# Sheet1.net
KiCad netlist of a schematic drawn in Altium Designer
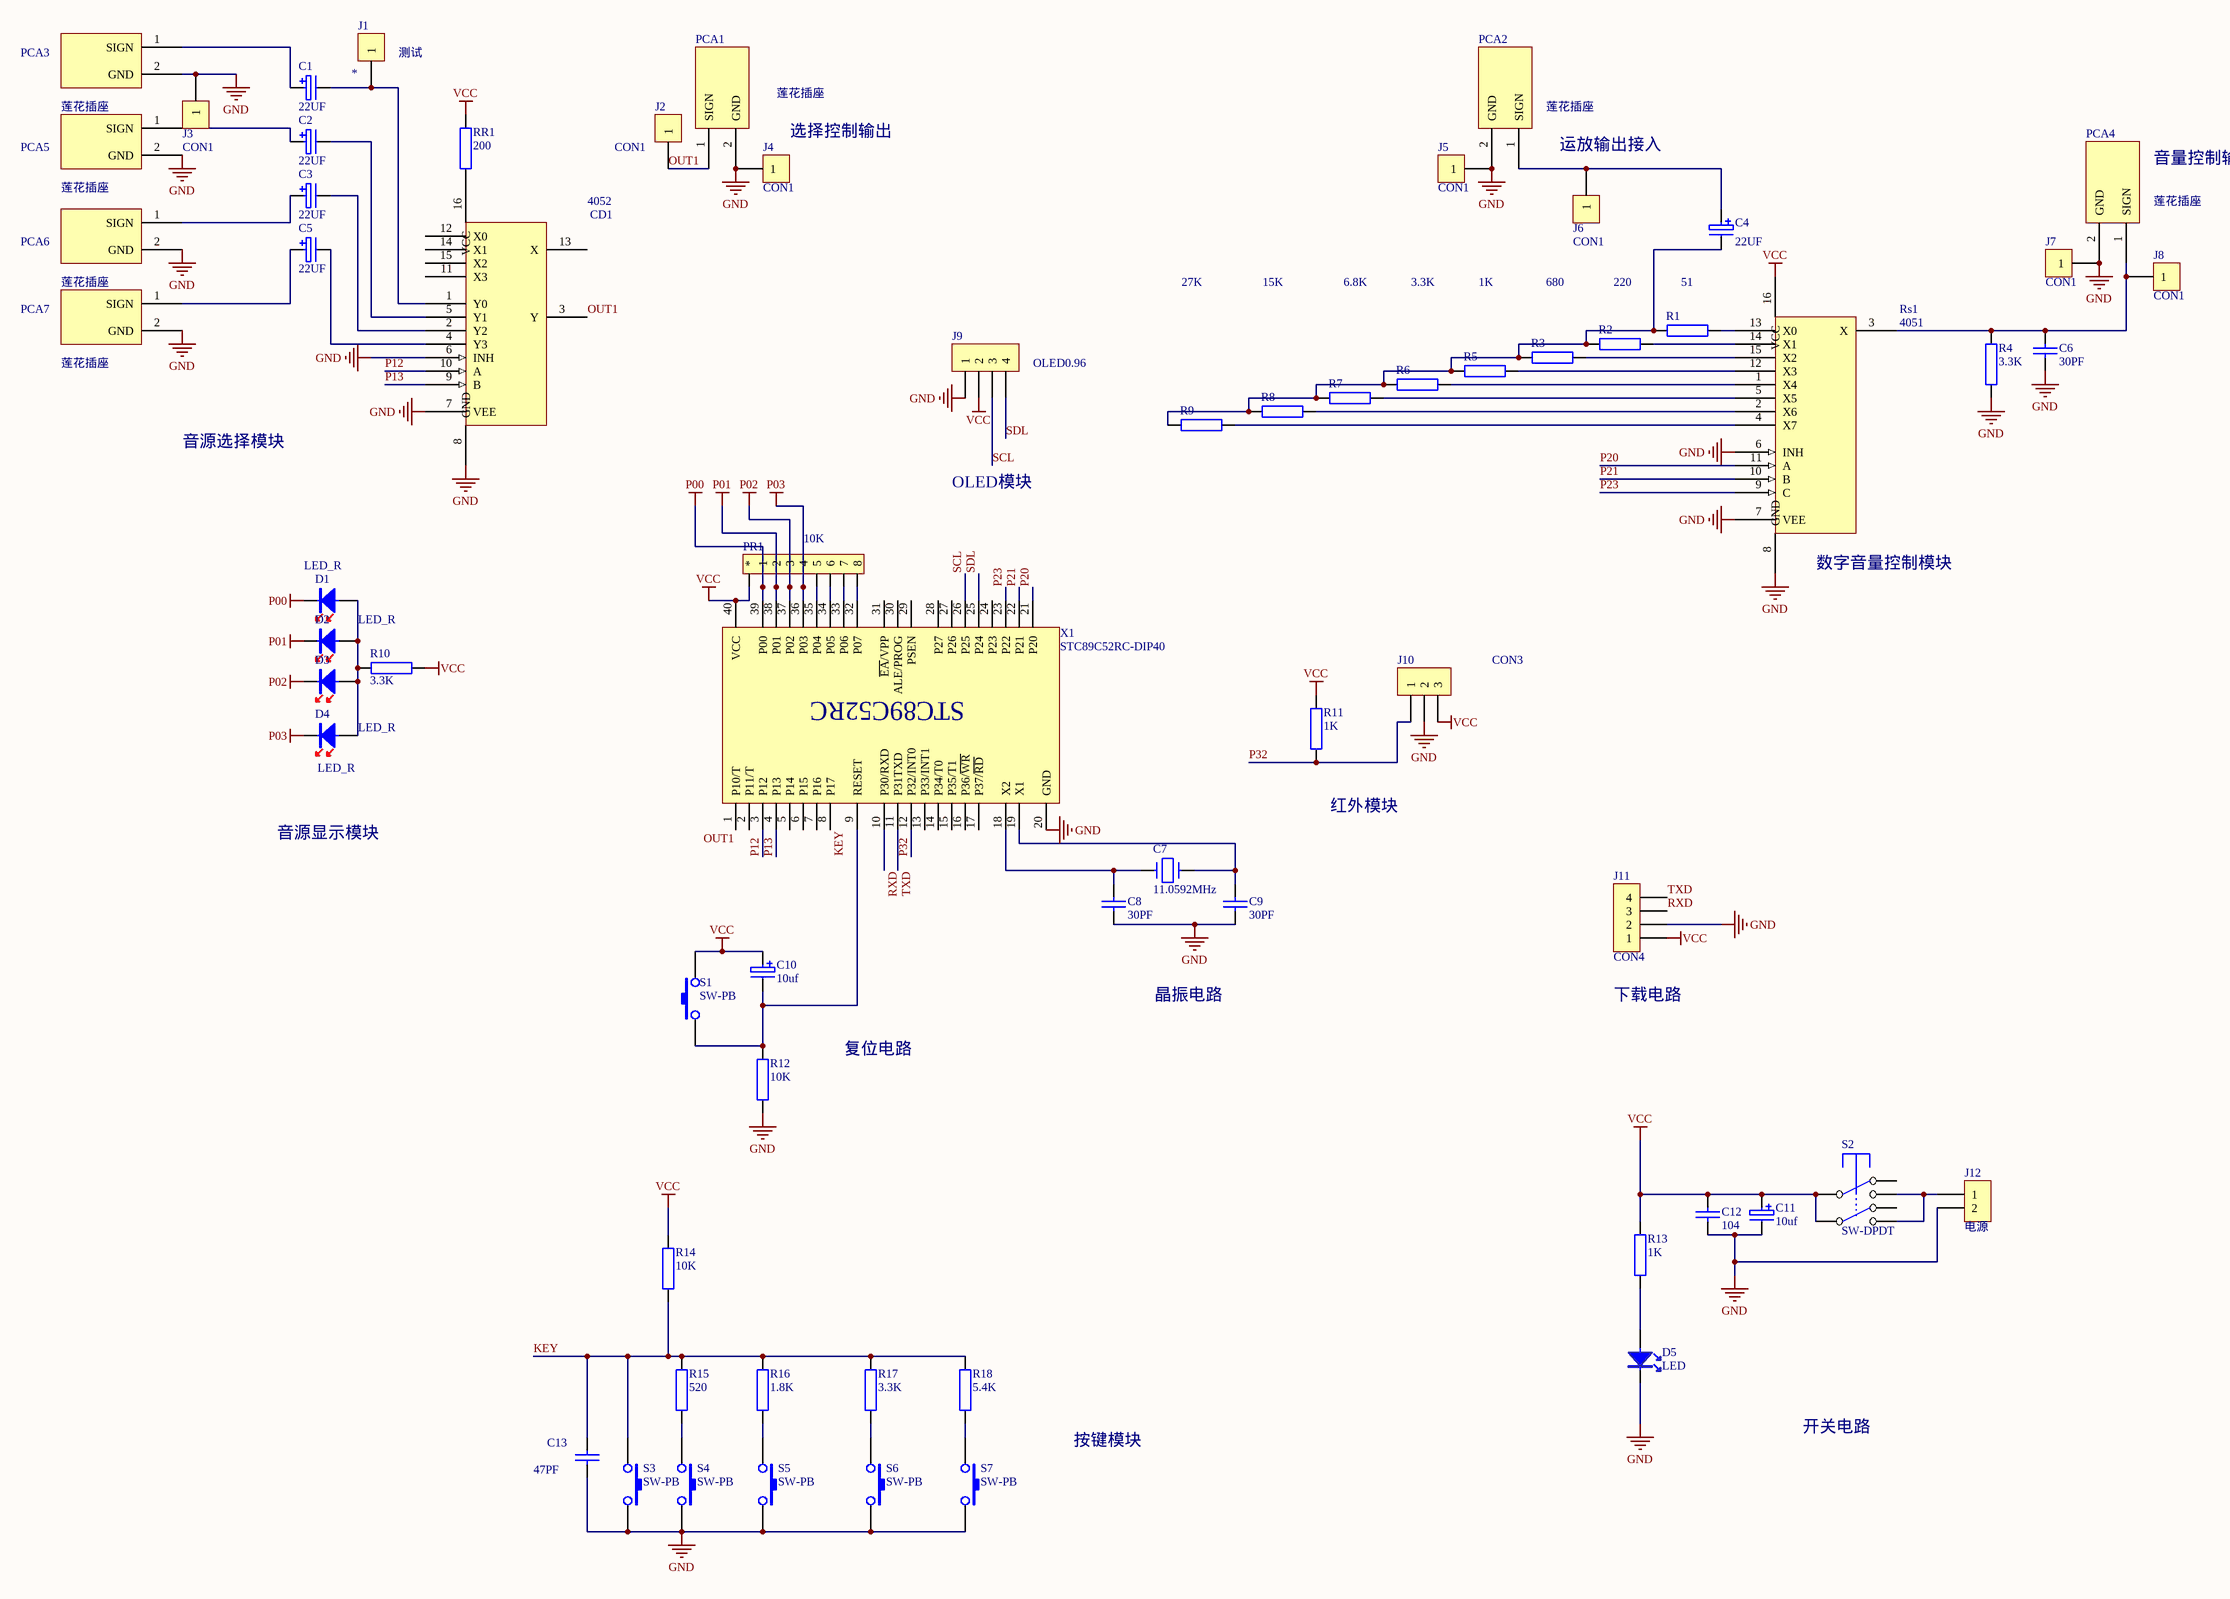
[diagram p0: Sheet1.SchDoc]

(export (version "E")
  (design (tool "Eeschema 10.0.6"))
  (components
    (comp (ref "C1") (value "22UF") (footprint "CAO2") (libsource (lib "电容") (part "CAP3")))
    (comp (ref "C2") (value "22UF") (footprint "CAO2") (libsource (lib "电容") (part "CAP3")))
    (comp (ref "C3") (value "22UF") (footprint "CAO2") (libsource (lib "电容") (part "CAP3")))
    (comp (ref "C4") (value "22UF") (footprint "CAO2") (libsource (lib "电容") (part "CAP3")))
    (comp (ref "C5") (value "22UF") (footprint "CAO2") (libsource (lib "电容") (part "CAP3")))
    (comp (ref "C6") (value "30PF") (footprint "CAP2") (libsource (lib "电容") (part "CAP1")))
    (comp (ref "C7") (value "11.0592MHz") (footprint "XTAL1") (libsource (lib "晶振") (part "CPY")))
    (comp (ref "C8") (value "30PF") (footprint "CAP2") (libsource (lib "电容") (part "CAP1")))
    (comp (ref "C9") (value "30PF") (footprint "CAP2") (libsource (lib "电容") (part "CAP1")))
    (comp (ref "C10") (value "10uf") (footprint "CAO2") (libsource (lib "电容") (part "CAP3")))
    (comp (ref "C11") (value "10uf") (footprint "CAO2") (libsource (lib "电容") (part "CAP3")))
    (comp (ref "C12") (value "104") (footprint "CAP2") (libsource (lib "电容") (part "CAP1")))
    (comp (ref "C13") (value "47PF") (footprint "CAP2") (libsource (lib "电容") (part "CAP1")))
    (comp (ref "CD1") (value "4052") (footprint "SO-16") (libsource (lib "51库") (part "4052")))
    (comp (ref "D1") (value "LED_R") (footprint "LED2_B") (libsource (lib "Diode二极管") (part "LED_R")))
    (comp (ref "D2") (value "LED_R") (footprint "LED2_B") (libsource (lib "Diode二极管") (part "LED_R")))
    (comp (ref "D3") (value "LED_R") (footprint "LED2_B") (libsource (lib "Diode二极管") (part "LED_R")))
    (comp (ref "D4") (value "LED_R") (footprint "LED2_B") (libsource (lib "Diode二极管") (part "LED_R")))
    (comp (ref "D5") (value "LED") (footprint "LED2_B") (libsource (lib "二极管") (part "LED")))
    (comp (ref "J1")
      (value "*")
      (footprint "SIP-1")
      (description "Connector")
      (fields (field (name "测试") "测试"))
      (libsource (lib "") (part "CON1_2"))
    )
    (comp (ref "J2")
      (value "CON1")
      (footprint "SIP-1")
      (description "Connector")
      (libsource (lib "") (part "CON1_2"))
    )
    (comp (ref "J3")
      (value "CON1")
      (footprint "SIP-1")
      (description "Connector")
      (libsource (lib "排针") (part "测试"))
    )
    (comp (ref "J4")
      (value "CON1")
      (footprint "SIP-1")
      (description "Connector")
      (libsource (lib "") (part "CON1_3"))
    )
    (comp (ref "J5")
      (value "CON1")
      (footprint "SIP-1")
      (description "Connector")
      (libsource (lib "") (part "CON1_1"))
    )
    (comp (ref "J6")
      (value "CON1")
      (footprint "SIP-1")
      (description "Connector")
      (libsource (lib "排针") (part "CON1"))
    )
    (comp (ref "J7")
      (value "CON1")
      (footprint "SIP-1")
      (description "Connector")
      (libsource (lib "") (part "CON1_1"))
    )
    (comp (ref "J8")
      (value "CON1")
      (footprint "SIP-1")
      (description "Connector")
      (libsource (lib "") (part "CON1_3"))
    )
    (comp (ref "J9")
      (value "OLED0.96")
      (footprint "sip-4")
      (description "Connector")
      (libsource (lib "排针") (part "CON4"))
    )
    (comp (ref "J10")
      (value "CON3")
      (footprint "sip-3")
      (description "Connector")
      (libsource (lib "排针") (part "CON3"))
    )
    (comp (ref "J11")
      (value "CON4")
      (footprint "sip-4")
      (description "Connector")
      (libsource (lib "") (part "CON4_1"))
    )
    (comp (ref "J12")
      (value "电源")
      (footprint "接线端子")
      (description "Connector")
      (libsource (lib "排针") (part "CON2"))
    )
    (comp (ref "PCA1") (value "莲花插座") (footprint "莲花母座") (libsource (lib "") (part "PCA_2")))
    (comp (ref "PCA2") (value "莲花插座") (footprint "莲花母座") (libsource (lib "") (part "PCA_1")))
    (comp (ref "PCA3") (value "莲花插座") (footprint "莲花母座") (libsource (lib "音频功放自画库") (part "PCA")))
    (comp (ref "PCA4") (value "莲花插座") (footprint "莲花母座") (libsource (lib "") (part "PCA_1")))
    (comp (ref "PCA5") (value "莲花插座") (footprint "莲花母座") (libsource (lib "音频功放自画库") (part "PCA")))
    (comp (ref "PCA6") (value "莲花插座") (footprint "莲花母座") (libsource (lib "音频功放自画库") (part "PCA")))
    (comp (ref "PCA7") (value "莲花插座") (footprint "莲花母座") (libsource (lib "音频功放自画库") (part "PCA")))
    (comp (ref "PR1") (value "10K") (footprint "RP1") (libsource (lib "电阻") (part "PRES1")))
    (comp (ref "R1")
      (value "51")
      (footprint "AXIAL0.4")
      (description "电阻")
      (libsource (lib "电阻") (part "RES"))
    )
    (comp (ref "R2")
      (value "220")
      (footprint "AXIAL0.4")
      (description "电阻")
      (libsource (lib "电阻") (part "RES"))
    )
    (comp (ref "R3")
      (value "680")
      (footprint "AXIAL0.4")
      (description "电阻")
      (libsource (lib "电阻") (part "RES"))
    )
    (comp (ref "R4")
      (value "3.3K")
      (footprint "AXIAL0.4")
      (description "电阻")
      (libsource (lib "电阻") (part "RES"))
    )
    (comp (ref "R5")
      (value "1K")
      (footprint "AXIAL0.4")
      (description "电阻")
      (libsource (lib "电阻") (part "RES"))
    )
    (comp (ref "R6")
      (value "3.3K")
      (footprint "AXIAL0.4")
      (description "电阻")
      (libsource (lib "电阻") (part "RES"))
    )
    (comp (ref "R7")
      (value "6.8K")
      (footprint "AXIAL0.4")
      (description "电阻")
      (libsource (lib "电阻") (part "RES"))
    )
    (comp (ref "R8")
      (value "15K")
      (footprint "AXIAL0.4")
      (description "电阻")
      (libsource (lib "电阻") (part "RES"))
    )
    (comp (ref "R9")
      (value "27K")
      (footprint "AXIAL0.4")
      (description "电阻")
      (libsource (lib "电阻") (part "RES"))
    )
    (comp (ref "R10")
      (value "3.3K")
      (footprint "AXIAL0.4")
      (description "电阻")
      (libsource (lib "电阻") (part "RES"))
    )
    (comp (ref "R11")
      (value "1K")
      (footprint "AXIAL0.4")
      (description "电阻")
      (libsource (lib "电阻") (part "RES"))
    )
    (comp (ref "R12")
      (value "10K")
      (footprint "AXIAL0.4")
      (description "电阻")
      (libsource (lib "电阻") (part "RES"))
    )
    (comp (ref "R13")
      (value "1K")
      (footprint "AXIAL0.4")
      (description "电阻")
      (libsource (lib "电阻") (part "RES"))
    )
    (comp (ref "R14")
      (value "10K")
      (footprint "AXIAL0.4")
      (description "电阻")
      (libsource (lib "电阻") (part "RES"))
    )
    (comp (ref "R15")
      (value "520")
      (footprint "AXIAL0.4")
      (description "电阻")
      (libsource (lib "电阻") (part "RES"))
    )
    (comp (ref "R16")
      (value "1.8K")
      (footprint "AXIAL0.4")
      (description "电阻")
      (libsource (lib "电阻") (part "RES"))
    )
    (comp (ref "R17")
      (value "3.3K")
      (footprint "AXIAL0.4")
      (description "电阻")
      (libsource (lib "电阻") (part "RES"))
    )
    (comp (ref "R18")
      (value "5.4K")
      (footprint "AXIAL0.4")
      (description "电阻")
      (libsource (lib "电阻") (part "RES"))
    )
    (comp (ref "RR1")
      (value "200")
      (footprint "AXIAL0.4")
      (description "电阻")
      (libsource (lib "电阻") (part "RES"))
    )
    (comp (ref "Rs1") (value "4051") (footprint "SO-16") (libsource (lib "51库") (part "4051")))
    (comp (ref "S1") (value "SW-PB") (footprint "SW6*6") (libsource (lib "开关") (part "SW-PB")))
    (comp (ref "S2") (value "SW-DPDT") (footprint "SWH8*8") (libsource (lib "开关") (part "SW-DPDT")))
    (comp (ref "S3") (value "SW-PB") (footprint "SW6*6") (libsource (lib "开关") (part "SW-PB")))
    (comp (ref "S4") (value "SW-PB") (footprint "SW6*6") (libsource (lib "开关") (part "SW-PB")))
    (comp (ref "S5") (value "SW-PB") (footprint "SW6*6") (libsource (lib "开关") (part "SW-PB")))
    (comp (ref "S6") (value "SW-PB") (footprint "SW6*6") (libsource (lib "开关") (part "SW-PB")))
    (comp (ref "S7") (value "SW-PB") (footprint "SW6*6") (libsource (lib "开关") (part "SW-PB")))
    (comp (ref "X1")
      (value "STC89C52RC-DIP40")
      (footprint "DIP-40")
      (libsource (lib "单片机") (part "STC89C52RC-DIP40"))
    )
  )
  (nets
    (net (code "1") (name "/KEY") (class "Default")
      (node (ref "C13") (pin "1") (pinfunction "1_1") (pintype "passive"))
      (node (ref "R14") (pin "1") (pinfunction "1_1") (pintype "passive"))
      (node (ref "R15") (pin "2") (pinfunction "2_2") (pintype "passive"))
      (node (ref "R16") (pin "2") (pinfunction "2_2") (pintype "passive"))
      (node (ref "R17") (pin "2") (pinfunction "2_2") (pintype "passive"))
      (node (ref "R18") (pin "2") (pinfunction "2_2") (pintype "passive"))
      (node (ref "S3") (pin "1") (pinfunction "1_1") (pintype "passive"))
      (node (ref "X1") (pin "8") (pinfunction "P17_8") (pintype "passive"))
    )
    (net (code "2") (name "/OUT1") (class "Default")
      (node (ref "CD1") (pin "3") (pinfunction "Y_3") (pintype "passive"))
      (node (ref "J2") (pin "1") (pinfunction "1_1") (pintype "passive"))
      (node (ref "PCA1") (pin "1") (pinfunction "SIGN_1") (pintype "passive"))
      (node (ref "X1") (pin "1") (pinfunction "P10/T_1") (pintype "passive"))
    )
    (net (code "3") (name "/P12") (class "Default")
      (node (ref "CD1") (pin "10") (pinfunction "A_10") (pintype "input"))
      (node (ref "X1") (pin "3") (pinfunction "P12_3") (pintype "passive"))
    )
    (net (code "4") (name "/P13") (class "Default")
      (node (ref "CD1") (pin "9") (pinfunction "B_9") (pintype "input"))
      (node (ref "X1") (pin "4") (pinfunction "P13_4") (pintype "passive"))
    )
    (net (code "5") (name "/P20") (class "Default")
      (node (ref "Rs1") (pin "11") (pinfunction "A_11") (pintype "input"))
      (node (ref "X1") (pin "21") (pinfunction "P20_21") (pintype "passive"))
    )
    (net (code "6") (name "/P21") (class "Default")
      (node (ref "Rs1") (pin "10") (pinfunction "B_10") (pintype "input"))
      (node (ref "X1") (pin "22") (pinfunction "P21_22") (pintype "passive"))
    )
    (net (code "7") (name "/P23") (class "Default")
      (node (ref "Rs1") (pin "9") (pinfunction "C_9") (pintype "input"))
      (node (ref "X1") (pin "23") (pinfunction "P22_23") (pintype "passive"))
    )
    (net (code "8") (name "/P32") (class "Default")
      (node (ref "J10") (pin "1") (pinfunction "1_1") (pintype "passive"))
      (node (ref "R11") (pin "1") (pinfunction "1_1") (pintype "passive"))
      (node (ref "X1") (pin "12") (pinfunction "P32/INT0_12") (pintype "passive"))
    )
    (net (code "9") (name "/RXD") (class "Default")
      (node (ref "J11") (pin "3") (pinfunction "3_3") (pintype "passive"))
      (node (ref "X1") (pin "10") (pinfunction "P30/RXD_10") (pintype "passive"))
    )
    (net (code "10") (name "/SCL") (class "Default")
      (node (ref "J9") (pin "3") (pinfunction "3_3") (pintype "passive"))
      (node (ref "X1") (pin "26") (pinfunction "P25_26") (pintype "passive"))
    )
    (net (code "11") (name "/SDL") (class "Default")
      (node (ref "J9") (pin "4") (pinfunction "4_4") (pintype "passive"))
      (node (ref "X1") (pin "25") (pinfunction "P24_25") (pintype "passive"))
    )
    (net (code "12") (name "/TXD") (class "Default")
      (node (ref "J11") (pin "4") (pinfunction "4_4") (pintype "passive"))
      (node (ref "X1") (pin "11") (pinfunction "P31TXD_11") (pintype "passive"))
    )
    (net (code "13") (name "GND") (class "Default")
      (node (ref "C11") (pin "2") (pintype "passive"))
      (node (ref "C12") (pin "2") (pinfunction "2_2") (pintype "passive"))
      (node (ref "C13") (pin "2") (pinfunction "2_2") (pintype "passive"))
      (node (ref "C6") (pin "2") (pinfunction "2_2") (pintype "passive"))
      (node (ref "C8") (pin "2") (pinfunction "2_2") (pintype "passive"))
      (node (ref "C9") (pin "2") (pinfunction "2_2") (pintype "passive"))
      (node (ref "CD1") (pin "6") (pinfunction "INH_6") (pintype "input"))
      (node (ref "CD1") (pin "7") (pinfunction "VEE_7") (pintype "passive"))
      (node (ref "CD1") (pin "8") (pinfunction "GND_8") (pintype "power_in"))
      (node (ref "D5") (pin "2") (pinfunction "2_2") (pintype "passive"))
      (node (ref "J10") (pin "2") (pinfunction "2_2") (pintype "passive"))
      (node (ref "J11") (pin "2") (pinfunction "2_2") (pintype "passive"))
      (node (ref "J12") (pin "2") (pinfunction "2_2") (pintype "passive"))
      (node (ref "J3") (pin "1") (pinfunction "1_1") (pintype "passive"))
      (node (ref "J4") (pin "1") (pinfunction "1_1") (pintype "passive"))
      (node (ref "J5") (pin "1") (pinfunction "1_1") (pintype "passive"))
      (node (ref "J7") (pin "1") (pinfunction "1_1") (pintype "passive"))
      (node (ref "J9") (pin "1") (pinfunction "1_1") (pintype "passive"))
      (node (ref "PCA1") (pin "2") (pinfunction "GND_2") (pintype "passive"))
      (node (ref "PCA2") (pin "2") (pinfunction "GND_2") (pintype "passive"))
      (node (ref "PCA3") (pin "2") (pinfunction "GND_2") (pintype "passive"))
      (node (ref "PCA4") (pin "2") (pinfunction "GND_2") (pintype "passive"))
      (node (ref "PCA5") (pin "2") (pinfunction "GND_2") (pintype "passive"))
      (node (ref "PCA6") (pin "2") (pinfunction "GND_2") (pintype "passive"))
      (node (ref "PCA7") (pin "2") (pinfunction "GND_2") (pintype "passive"))
      (node (ref "R12") (pin "1") (pinfunction "1_1") (pintype "passive"))
      (node (ref "R4") (pin "1") (pinfunction "1_1") (pintype "passive"))
      (node (ref "Rs1") (pin "6") (pinfunction "INH_6") (pintype "input"))
      (node (ref "Rs1") (pin "7") (pinfunction "VEE_7") (pintype "passive"))
      (node (ref "Rs1") (pin "8") (pinfunction "GND_8") (pintype "power_in"))
      (node (ref "S3") (pin "2") (pinfunction "2_2") (pintype "passive"))
      (node (ref "S4") (pin "2") (pinfunction "2_2") (pintype "passive"))
      (node (ref "S5") (pin "2") (pinfunction "2_2") (pintype "passive"))
      (node (ref "S6") (pin "2") (pinfunction "2_2") (pintype "passive"))
      (node (ref "S7") (pin "2") (pinfunction "2_2") (pintype "passive"))
      (node (ref "X1") (pin "20") (pinfunction "GND_20") (pintype "passive"))
    )
    (net (code "14") (name "Net-(C4-Pad2)") (class "Default")
      (node (ref "C4") (pin "2") (pintype "passive"))
      (node (ref "R1") (pin "1") (pinfunction "1_1") (pintype "passive"))
      (node (ref "R2") (pin "1") (pinfunction "1_1") (pintype "passive"))
      (node (ref "R3") (pin "1") (pinfunction "1_1") (pintype "passive"))
      (node (ref "R5") (pin "1") (pinfunction "1_1") (pintype "passive"))
      (node (ref "R6") (pin "1") (pinfunction "1_1") (pintype "passive"))
      (node (ref "R7") (pin "1") (pinfunction "1_1") (pintype "passive"))
      (node (ref "R8") (pin "1") (pinfunction "1_1") (pintype "passive"))
      (node (ref "R9") (pin "1") (pinfunction "1_1") (pintype "passive"))
    )
    (net (code "15") (name "Net-(CD1-VCC)") (class "Default")
      (node (ref "CD1") (pin "16") (pinfunction "VCC_16") (pintype "power_in"))
      (node (ref "RR1") (pin "2") (pinfunction "2_2") (pintype "passive"))
    )
    (net (code "16") (name "Net-(CD1-Y0)") (class "Default")
      (node (ref "C1") (pin "2") (pintype "passive"))
      (node (ref "CD1") (pin "1") (pinfunction "Y0_1") (pintype "passive"))
      (node (ref "J1") (pin "1") (pinfunction "1_1") (pintype "passive"))
    )
    (net (code "17") (name "Net-(CD1-Y1)") (class "Default")
      (node (ref "C2") (pin "2") (pintype "passive"))
      (node (ref "CD1") (pin "5") (pinfunction "Y1_5") (pintype "passive"))
    )
    (net (code "18") (name "Net-(CD1-Y2)") (class "Default")
      (node (ref "C3") (pin "2") (pintype "passive"))
      (node (ref "CD1") (pin "2") (pinfunction "Y2_2") (pintype "passive"))
    )
    (net (code "19") (name "Net-(CD1-Y3)") (class "Default")
      (node (ref "C5") (pin "2") (pintype "passive"))
      (node (ref "CD1") (pin "4") (pinfunction "Y3_4") (pintype "passive"))
    )
    (net (code "20") (name "Net-(D1-Pad1)") (class "Default")
      (node (ref "D1") (pin "1") (pinfunction "1_1") (pintype "passive"))
      (node (ref "D2") (pin "1") (pinfunction "1_1") (pintype "passive"))
      (node (ref "D3") (pin "1") (pinfunction "1_1") (pintype "passive"))
      (node (ref "D4") (pin "1") (pinfunction "1_1") (pintype "passive"))
      (node (ref "R10") (pin "2") (pinfunction "2_2") (pintype "passive"))
    )
    (net (code "21") (name "Net-(D5-Pad1)") (class "Default")
      (node (ref "D5") (pin "1") (pinfunction "1_1") (pintype "passive"))
      (node (ref "R13") (pin "1") (pinfunction "1_1") (pintype "passive"))
    )
    (net (code "22") (name "Net-(J12-Pad1)") (class "Default")
      (node (ref "J12") (pin "1") (pinfunction "1_1") (pintype "passive"))
      (node (ref "S2") (pin "3") (pinfunction "3_3") (pintype "passive"))
      (node (ref "S2") (pin "4") (pinfunction "4_4") (pintype "passive"))
    )
    (net (code "23") (name "Net-(PCA2-SIGN)") (class "Default")
      (node (ref "C4") (pin "1") (pintype "passive"))
      (node (ref "J6") (pin "1") (pinfunction "1_1") (pintype "passive"))
      (node (ref "PCA2") (pin "1") (pinfunction "SIGN_1") (pintype "passive"))
    )
    (net (code "24") (name "Net-(PCA3-SIGN)") (class "Default")
      (node (ref "C1") (pin "1") (pintype "passive"))
      (node (ref "PCA3") (pin "1") (pinfunction "SIGN_1") (pintype "passive"))
    )
    (net (code "25") (name "Net-(PCA4-SIGN)") (class "Default")
      (node (ref "C6") (pin "1") (pinfunction "1_1") (pintype "passive"))
      (node (ref "J8") (pin "1") (pinfunction "1_1") (pintype "passive"))
      (node (ref "PCA4") (pin "1") (pinfunction "SIGN_1") (pintype "passive"))
      (node (ref "R4") (pin "2") (pinfunction "2_2") (pintype "passive"))
      (node (ref "Rs1") (pin "3") (pinfunction "X_3") (pintype "passive"))
    )
    (net (code "26") (name "Net-(PCA5-SIGN)") (class "Default")
      (node (ref "C2") (pin "1") (pintype "passive"))
      (node (ref "PCA5") (pin "1") (pinfunction "SIGN_1") (pintype "passive"))
    )
    (net (code "27") (name "Net-(PCA6-SIGN)") (class "Default")
      (node (ref "C3") (pin "1") (pintype "passive"))
      (node (ref "PCA6") (pin "1") (pinfunction "SIGN_1") (pintype "passive"))
    )
    (net (code "28") (name "Net-(PCA7-SIGN)") (class "Default")
      (node (ref "C5") (pin "1") (pintype "passive"))
      (node (ref "PCA7") (pin "1") (pinfunction "SIGN_1") (pintype "passive"))
    )
    (net (code "29") (name "Net-(PR1-5)") (class "Default")
      (node (ref "PR1") (pin "6") (pinfunction "5_6") (pintype "passive"))
      (node (ref "X1") (pin "35") (pinfunction "P04_35") (pintype "passive"))
    )
    (net (code "30") (name "Net-(PR1-6)") (class "Default")
      (node (ref "PR1") (pin "7") (pinfunction "6_7") (pintype "passive"))
      (node (ref "X1") (pin "34") (pinfunction "P05_34") (pintype "passive"))
    )
    (net (code "31") (name "Net-(PR1-7)") (class "Default")
      (node (ref "PR1") (pin "8") (pinfunction "7_8") (pintype "passive"))
      (node (ref "X1") (pin "33") (pinfunction "P06_33") (pintype "passive"))
    )
    (net (code "32") (name "Net-(PR1-8)") (class "Default")
      (node (ref "PR1") (pin "9") (pinfunction "8_9") (pintype "passive"))
      (node (ref "X1") (pin "32") (pinfunction "P07_32") (pintype "passive"))
    )
    (net (code "33") (name "Net-(R15-Pad1)") (class "Default")
      (node (ref "R15") (pin "1") (pinfunction "1_1") (pintype "passive"))
      (node (ref "S4") (pin "1") (pinfunction "1_1") (pintype "passive"))
    )
    (net (code "34") (name "Net-(R16-Pad1)") (class "Default")
      (node (ref "R16") (pin "1") (pinfunction "1_1") (pintype "passive"))
      (node (ref "S5") (pin "1") (pinfunction "1_1") (pintype "passive"))
    )
    (net (code "35") (name "Net-(R17-Pad1)") (class "Default")
      (node (ref "R17") (pin "1") (pinfunction "1_1") (pintype "passive"))
      (node (ref "S6") (pin "1") (pinfunction "1_1") (pintype "passive"))
    )
    (net (code "36") (name "Net-(R18-Pad1)") (class "Default")
      (node (ref "R18") (pin "1") (pinfunction "1_1") (pintype "passive"))
      (node (ref "S7") (pin "1") (pinfunction "1_1") (pintype "passive"))
    )
    (net (code "37") (name "Net-(Rs1-X0)") (class "Default")
      (node (ref "R1") (pin "2") (pinfunction "2_2") (pintype "passive"))
      (node (ref "Rs1") (pin "13") (pinfunction "X0_13") (pintype "passive"))
    )
    (net (code "38") (name "Net-(Rs1-X1)") (class "Default")
      (node (ref "R2") (pin "2") (pinfunction "2_2") (pintype "passive"))
      (node (ref "Rs1") (pin "14") (pinfunction "X1_14") (pintype "passive"))
    )
    (net (code "39") (name "Net-(Rs1-X2)") (class "Default")
      (node (ref "R3") (pin "2") (pinfunction "2_2") (pintype "passive"))
      (node (ref "Rs1") (pin "15") (pinfunction "X2_15") (pintype "passive"))
    )
    (net (code "40") (name "Net-(Rs1-X3)") (class "Default")
      (node (ref "R5") (pin "2") (pinfunction "2_2") (pintype "passive"))
      (node (ref "Rs1") (pin "12") (pinfunction "X3_12") (pintype "passive"))
    )
    (net (code "41") (name "Net-(Rs1-X4)") (class "Default")
      (node (ref "R6") (pin "2") (pinfunction "2_2") (pintype "passive"))
      (node (ref "Rs1") (pin "1") (pinfunction "X4_1") (pintype "passive"))
    )
    (net (code "42") (name "Net-(Rs1-X5)") (class "Default")
      (node (ref "R7") (pin "2") (pinfunction "2_2") (pintype "passive"))
      (node (ref "Rs1") (pin "5") (pinfunction "X5_5") (pintype "passive"))
    )
    (net (code "43") (name "Net-(Rs1-X6)") (class "Default")
      (node (ref "R8") (pin "2") (pinfunction "2_2") (pintype "passive"))
      (node (ref "Rs1") (pin "2") (pinfunction "X6_2") (pintype "passive"))
    )
    (net (code "44") (name "Net-(Rs1-X7)") (class "Default")
      (node (ref "R9") (pin "2") (pinfunction "2_2") (pintype "passive"))
      (node (ref "Rs1") (pin "4") (pinfunction "X7_4") (pintype "passive"))
    )
    (net (code "45") (name "Net-(X1-RESET)") (class "Default")
      (node (ref "C10") (pin "2") (pintype "passive"))
      (node (ref "R12") (pin "2") (pinfunction "2_2") (pintype "passive"))
      (node (ref "S1") (pin "1") (pinfunction "1_1") (pintype "passive"))
      (node (ref "X1") (pin "9") (pinfunction "RESET_9") (pintype "passive"))
    )
    (net (code "46") (name "Net-(X1-X1)") (class "Default")
      (node (ref "C7") (pin "2") (pintype "passive"))
      (node (ref "C9") (pin "1") (pinfunction "1_1") (pintype "passive"))
      (node (ref "X1") (pin "19") (pinfunction "X1_19") (pintype "passive"))
    )
    (net (code "47") (name "Net-(X1-X2)") (class "Default")
      (node (ref "C7") (pin "1") (pintype "passive"))
      (node (ref "C8") (pin "1") (pinfunction "1_1") (pintype "passive"))
      (node (ref "X1") (pin "18") (pinfunction "X2_18") (pintype "passive"))
    )
    (net (code "48") (name "P00") (class "Default")
      (node (ref "D1") (pin "2") (pinfunction "2_2") (pintype "passive"))
      (node (ref "PR1") (pin "2") (pinfunction "1_2") (pintype "passive"))
      (node (ref "X1") (pin "39") (pinfunction "P00_39") (pintype "passive"))
    )
    (net (code "49") (name "P01") (class "Default")
      (node (ref "D2") (pin "2") (pinfunction "2_2") (pintype "passive"))
      (node (ref "PR1") (pin "3") (pinfunction "2_3") (pintype "passive"))
      (node (ref "X1") (pin "38") (pinfunction "P01_38") (pintype "passive"))
    )
    (net (code "50") (name "P02") (class "Default")
      (node (ref "D3") (pin "2") (pinfunction "2_2") (pintype "passive"))
      (node (ref "PR1") (pin "4") (pinfunction "3_4") (pintype "passive"))
      (node (ref "X1") (pin "37") (pinfunction "P02_37") (pintype "passive"))
    )
    (net (code "51") (name "P03") (class "Default")
      (node (ref "D4") (pin "2") (pinfunction "2_2") (pintype "passive"))
      (node (ref "PR1") (pin "5") (pinfunction "4_5") (pintype "passive"))
      (node (ref "X1") (pin "36") (pinfunction "P03_36") (pintype "passive"))
    )
    (net (code "52") (name "VCC") (class "Default")
      (node (ref "C10") (pin "1") (pintype "passive"))
      (node (ref "C11") (pin "1") (pintype "passive"))
      (node (ref "C12") (pin "1") (pinfunction "1_1") (pintype "passive"))
      (node (ref "J10") (pin "3") (pinfunction "3_3") (pintype "passive"))
      (node (ref "J11") (pin "1") (pinfunction "1_1") (pintype "passive"))
      (node (ref "J9") (pin "2") (pinfunction "2_2") (pintype "passive"))
      (node (ref "PR1") (pin "1") (pinfunction "*_1") (pintype "passive"))
      (node (ref "R10") (pin "1") (pinfunction "1_1") (pintype "passive"))
      (node (ref "R11") (pin "2") (pinfunction "2_2") (pintype "passive"))
      (node (ref "R13") (pin "2") (pinfunction "2_2") (pintype "passive"))
      (node (ref "R14") (pin "2") (pinfunction "2_2") (pintype "passive"))
      (node (ref "RR1") (pin "1") (pinfunction "1_1") (pintype "passive"))
      (node (ref "Rs1") (pin "16") (pinfunction "VCC_16") (pintype "power_in"))
      (node (ref "S1") (pin "2") (pinfunction "2_2") (pintype "passive"))
      (node (ref "S2") (pin "2") (pinfunction "2_2") (pintype "passive"))
      (node (ref "S2") (pin "5") (pinfunction "5_5") (pintype "passive"))
      (node (ref "X1") (pin "40") (pinfunction "VCC_40") (pintype "passive"))
    )
    (net (code "53") (name "unconnected-(CD1-X-Pad13)") (class "Default")
      (node (ref "CD1") (pin "13") (pinfunction "X_13") (pintype "passive"))
    )
    (net (code "54") (name "unconnected-(CD1-X0-Pad12)") (class "Default")
      (node (ref "CD1") (pin "12") (pinfunction "X0_12") (pintype "passive"))
    )
    (net (code "55") (name "unconnected-(CD1-X1-Pad14)") (class "Default")
      (node (ref "CD1") (pin "14") (pinfunction "X1_14") (pintype "passive"))
    )
    (net (code "56") (name "unconnected-(CD1-X2-Pad15)") (class "Default")
      (node (ref "CD1") (pin "15") (pinfunction "X2_15") (pintype "passive"))
    )
    (net (code "57") (name "unconnected-(CD1-X3-Pad11)") (class "Default")
      (node (ref "CD1") (pin "11") (pinfunction "X3_11") (pintype "passive"))
    )
    (net (code "58") (name "unconnected-(S2-Pad1)") (class "Default")
      (node (ref "S2") (pin "1") (pinfunction "1_1") (pintype "passive"))
    )
    (net (code "59") (name "unconnected-(S2-Pad6)") (class "Default")
      (node (ref "S2") (pin "6") (pinfunction "6_6") (pintype "passive"))
    )
    (net (code "60") (name "unconnected-(X1-ALE{slash}PROG-Pad30)") (class "Default")
      (node (ref "X1") (pin "30") (pinfunction "ALE/PROG_30") (pintype "passive"))
    )
    (net (code "61") (name "unconnected-(X1-P11{slash}T-Pad2)") (class "Default")
      (node (ref "X1") (pin "2") (pinfunction "P11/T_2") (pintype "passive"))
    )
    (net (code "62") (name "unconnected-(X1-P14-Pad5)") (class "Default")
      (node (ref "X1") (pin "5") (pinfunction "P14_5") (pintype "passive"))
    )
    (net (code "63") (name "unconnected-(X1-P15-Pad6)") (class "Default")
      (node (ref "X1") (pin "6") (pinfunction "P15_6") (pintype "passive"))
    )
    (net (code "64") (name "unconnected-(X1-P16-Pad7)") (class "Default")
      (node (ref "X1") (pin "7") (pinfunction "P16_7") (pintype "passive"))
    )
    (net (code "65") (name "unconnected-(X1-P23-Pad24)") (class "Default")
      (node (ref "X1") (pin "24") (pinfunction "P23_24") (pintype "passive"))
    )
    (net (code "66") (name "unconnected-(X1-P26-Pad27)") (class "Default")
      (node (ref "X1") (pin "27") (pinfunction "P26_27") (pintype "passive"))
    )
    (net (code "67") (name "unconnected-(X1-P27-Pad28)") (class "Default")
      (node (ref "X1") (pin "28") (pinfunction "P27_28") (pintype "passive"))
    )
    (net (code "68") (name "unconnected-(X1-P33{slash}INT1-Pad13)") (class "Default")
      (node (ref "X1") (pin "13") (pinfunction "P33/INT1_13") (pintype "passive"))
    )
    (net (code "69") (name "unconnected-(X1-P34{slash}T0-Pad14)") (class "Default")
      (node (ref "X1") (pin "14") (pinfunction "P34/T0_14") (pintype "passive"))
    )
    (net (code "70") (name "unconnected-(X1-P35{slash}T1-Pad15)") (class "Default")
      (node (ref "X1") (pin "15") (pinfunction "P35/T1_15") (pintype "passive"))
    )
    (net (code "71") (name "unconnected-(X1-P36{slash}~{WR}-Pad16)") (class "Default")
      (node (ref "X1") (pin "16") (pinfunction "P36/~{WR}_16") (pintype "passive"))
    )
    (net (code "72") (name "unconnected-(X1-P37{slash}~{RD}-Pad17)") (class "Default")
      (node (ref "X1") (pin "17") (pinfunction "P37/~{RD}_17") (pintype "passive"))
    )
    (net (code "73") (name "unconnected-(X1-PSEN-Pad29)") (class "Default")
      (node (ref "X1") (pin "29") (pinfunction "PSEN_29") (pintype "passive"))
    )
    (net (code "74") (name "unconnected-(X1-~{EA}{slash}VPP-Pad31)") (class "Default")
      (node (ref "X1") (pin "31") (pinfunction "~{EA}/VPP_31") (pintype "passive"))
    )
  )
)
